# SOT23-6-minimal.net
KiCad netlist of a schematic drawn in EAGLE
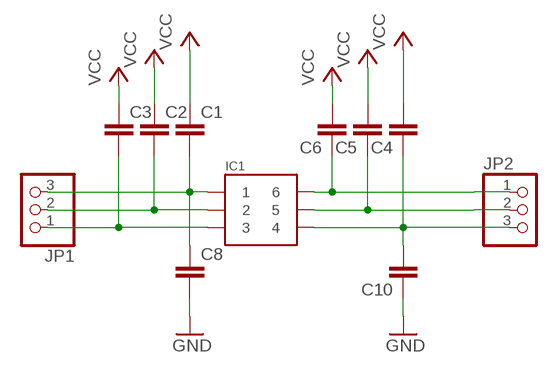
[diagram p0: schematic, sheet 1]

(export (version "E")
  (design (tool "Eeschema 10.0.6"))
  (components
    (comp (ref "C1")
      (value "C-EUC0603")
      (footprint "eagle-import:C0603")
      (libsource (lib "eagle-import") (part "C-EUC0603"))
    )
    (comp (ref "C2")
      (value "C-EUC0603")
      (footprint "eagle-import:C0603")
      (libsource (lib "eagle-import") (part "C-EUC0603"))
    )
    (comp (ref "C3")
      (value "C-EUC0603")
      (footprint "eagle-import:C0603")
      (libsource (lib "eagle-import") (part "C-EUC0603"))
    )
    (comp (ref "C4")
      (value "C-EUC0603")
      (footprint "eagle-import:C0603")
      (libsource (lib "eagle-import") (part "C-EUC0603"))
    )
    (comp (ref "C5")
      (value "C-EUC0603")
      (footprint "eagle-import:C0603")
      (libsource (lib "eagle-import") (part "C-EUC0603"))
    )
    (comp (ref "C6")
      (value "C-EUC0603")
      (footprint "eagle-import:C0603")
      (libsource (lib "eagle-import") (part "C-EUC0603"))
    )
    (comp (ref "C8")
      (value "C-EUC0603")
      (footprint "eagle-import:C0603")
      (libsource (lib "eagle-import") (part "C-EUC0603"))
    )
    (comp (ref "C10")
      (value "C-EUC0603")
      (footprint "eagle-import:C0603")
      (libsource (lib "eagle-import") (part "C-EUC0603"))
    )
    (comp (ref "IC1")
      (value "2X3-PIN-SOT23")
      (footprint "eagle-import:SOT23-6")
      (libsource (lib "eagle-import") (part "2X3-PIN-SOT23"))
    )
    (comp (ref "JP1")
      (value "PINHD-1X3")
      (footprint "eagle-import:1X03")
      (libsource (lib "eagle-import") (part "PINHD-1X3"))
    )
    (comp (ref "JP2")
      (value "PINHD-1X3")
      (footprint "eagle-import:1X03")
      (libsource (lib "eagle-import") (part "PINHD-1X3"))
    )
  )
  (nets
    (net (code "1") (name "GND") (class "Default")
      (node (ref "C10") (pin "1") (pinfunction "1_1") (pintype "passive"))
      (node (ref "C8") (pin "2") (pinfunction "2_2") (pintype "passive"))
    )
    (net (code "2") (name "Net-(IC1-1)") (class "Default")
      (node (ref "C1") (pin "2") (pinfunction "2_2") (pintype "passive"))
      (node (ref "C8") (pin "1") (pinfunction "1_1") (pintype "passive"))
      (node (ref "IC1") (pin "P$1") (pinfunction "1_P$1") (pintype "bidirectional"))
      (node (ref "JP1") (pin "3") (pinfunction "3_3") (pintype "passive"))
    )
    (net (code "3") (name "Net-(IC1-2)") (class "Default")
      (node (ref "C2") (pin "2") (pinfunction "2_2") (pintype "passive"))
      (node (ref "IC1") (pin "P$2") (pinfunction "2_P$2") (pintype "bidirectional"))
      (node (ref "JP1") (pin "2") (pinfunction "2_2") (pintype "passive"))
    )
    (net (code "4") (name "Net-(IC1-3)") (class "Default")
      (node (ref "C3") (pin "2") (pinfunction "2_2") (pintype "passive"))
      (node (ref "IC1") (pin "P$3") (pinfunction "3_P$3") (pintype "bidirectional"))
      (node (ref "JP1") (pin "1") (pinfunction "1_1") (pintype "passive"))
    )
    (net (code "5") (name "Net-(IC1-4)") (class "Default")
      (node (ref "C10") (pin "2") (pinfunction "2_2") (pintype "passive"))
      (node (ref "C4") (pin "1") (pinfunction "1_1") (pintype "passive"))
      (node (ref "IC1") (pin "P$4") (pinfunction "4_P$4") (pintype "bidirectional"))
      (node (ref "JP2") (pin "3") (pinfunction "3_3") (pintype "passive"))
    )
    (net (code "6") (name "Net-(IC1-5)") (class "Default")
      (node (ref "C5") (pin "1") (pinfunction "1_1") (pintype "passive"))
      (node (ref "IC1") (pin "P$5") (pinfunction "5_P$5") (pintype "bidirectional"))
      (node (ref "JP2") (pin "2") (pinfunction "2_2") (pintype "passive"))
    )
    (net (code "7") (name "Net-(IC1-6)") (class "Default")
      (node (ref "C6") (pin "1") (pinfunction "1_1") (pintype "passive"))
      (node (ref "IC1") (pin "P$6") (pinfunction "6_P$6") (pintype "bidirectional"))
      (node (ref "JP2") (pin "1") (pinfunction "1_1") (pintype "passive"))
    )
    (net (code "8") (name "VCC") (class "Default")
      (node (ref "C1") (pin "1") (pinfunction "1_1") (pintype "passive"))
      (node (ref "C2") (pin "1") (pinfunction "1_1") (pintype "passive"))
      (node (ref "C3") (pin "1") (pinfunction "1_1") (pintype "passive"))
      (node (ref "C4") (pin "2") (pinfunction "2_2") (pintype "passive"))
      (node (ref "C5") (pin "2") (pinfunction "2_2") (pintype "passive"))
      (node (ref "C6") (pin "2") (pinfunction "2_2") (pintype "passive"))
    )
  )
)
